# Power_and_Decoupling_Capacitors.net
KiCad netlist of a schematic drawn in Altium Designer
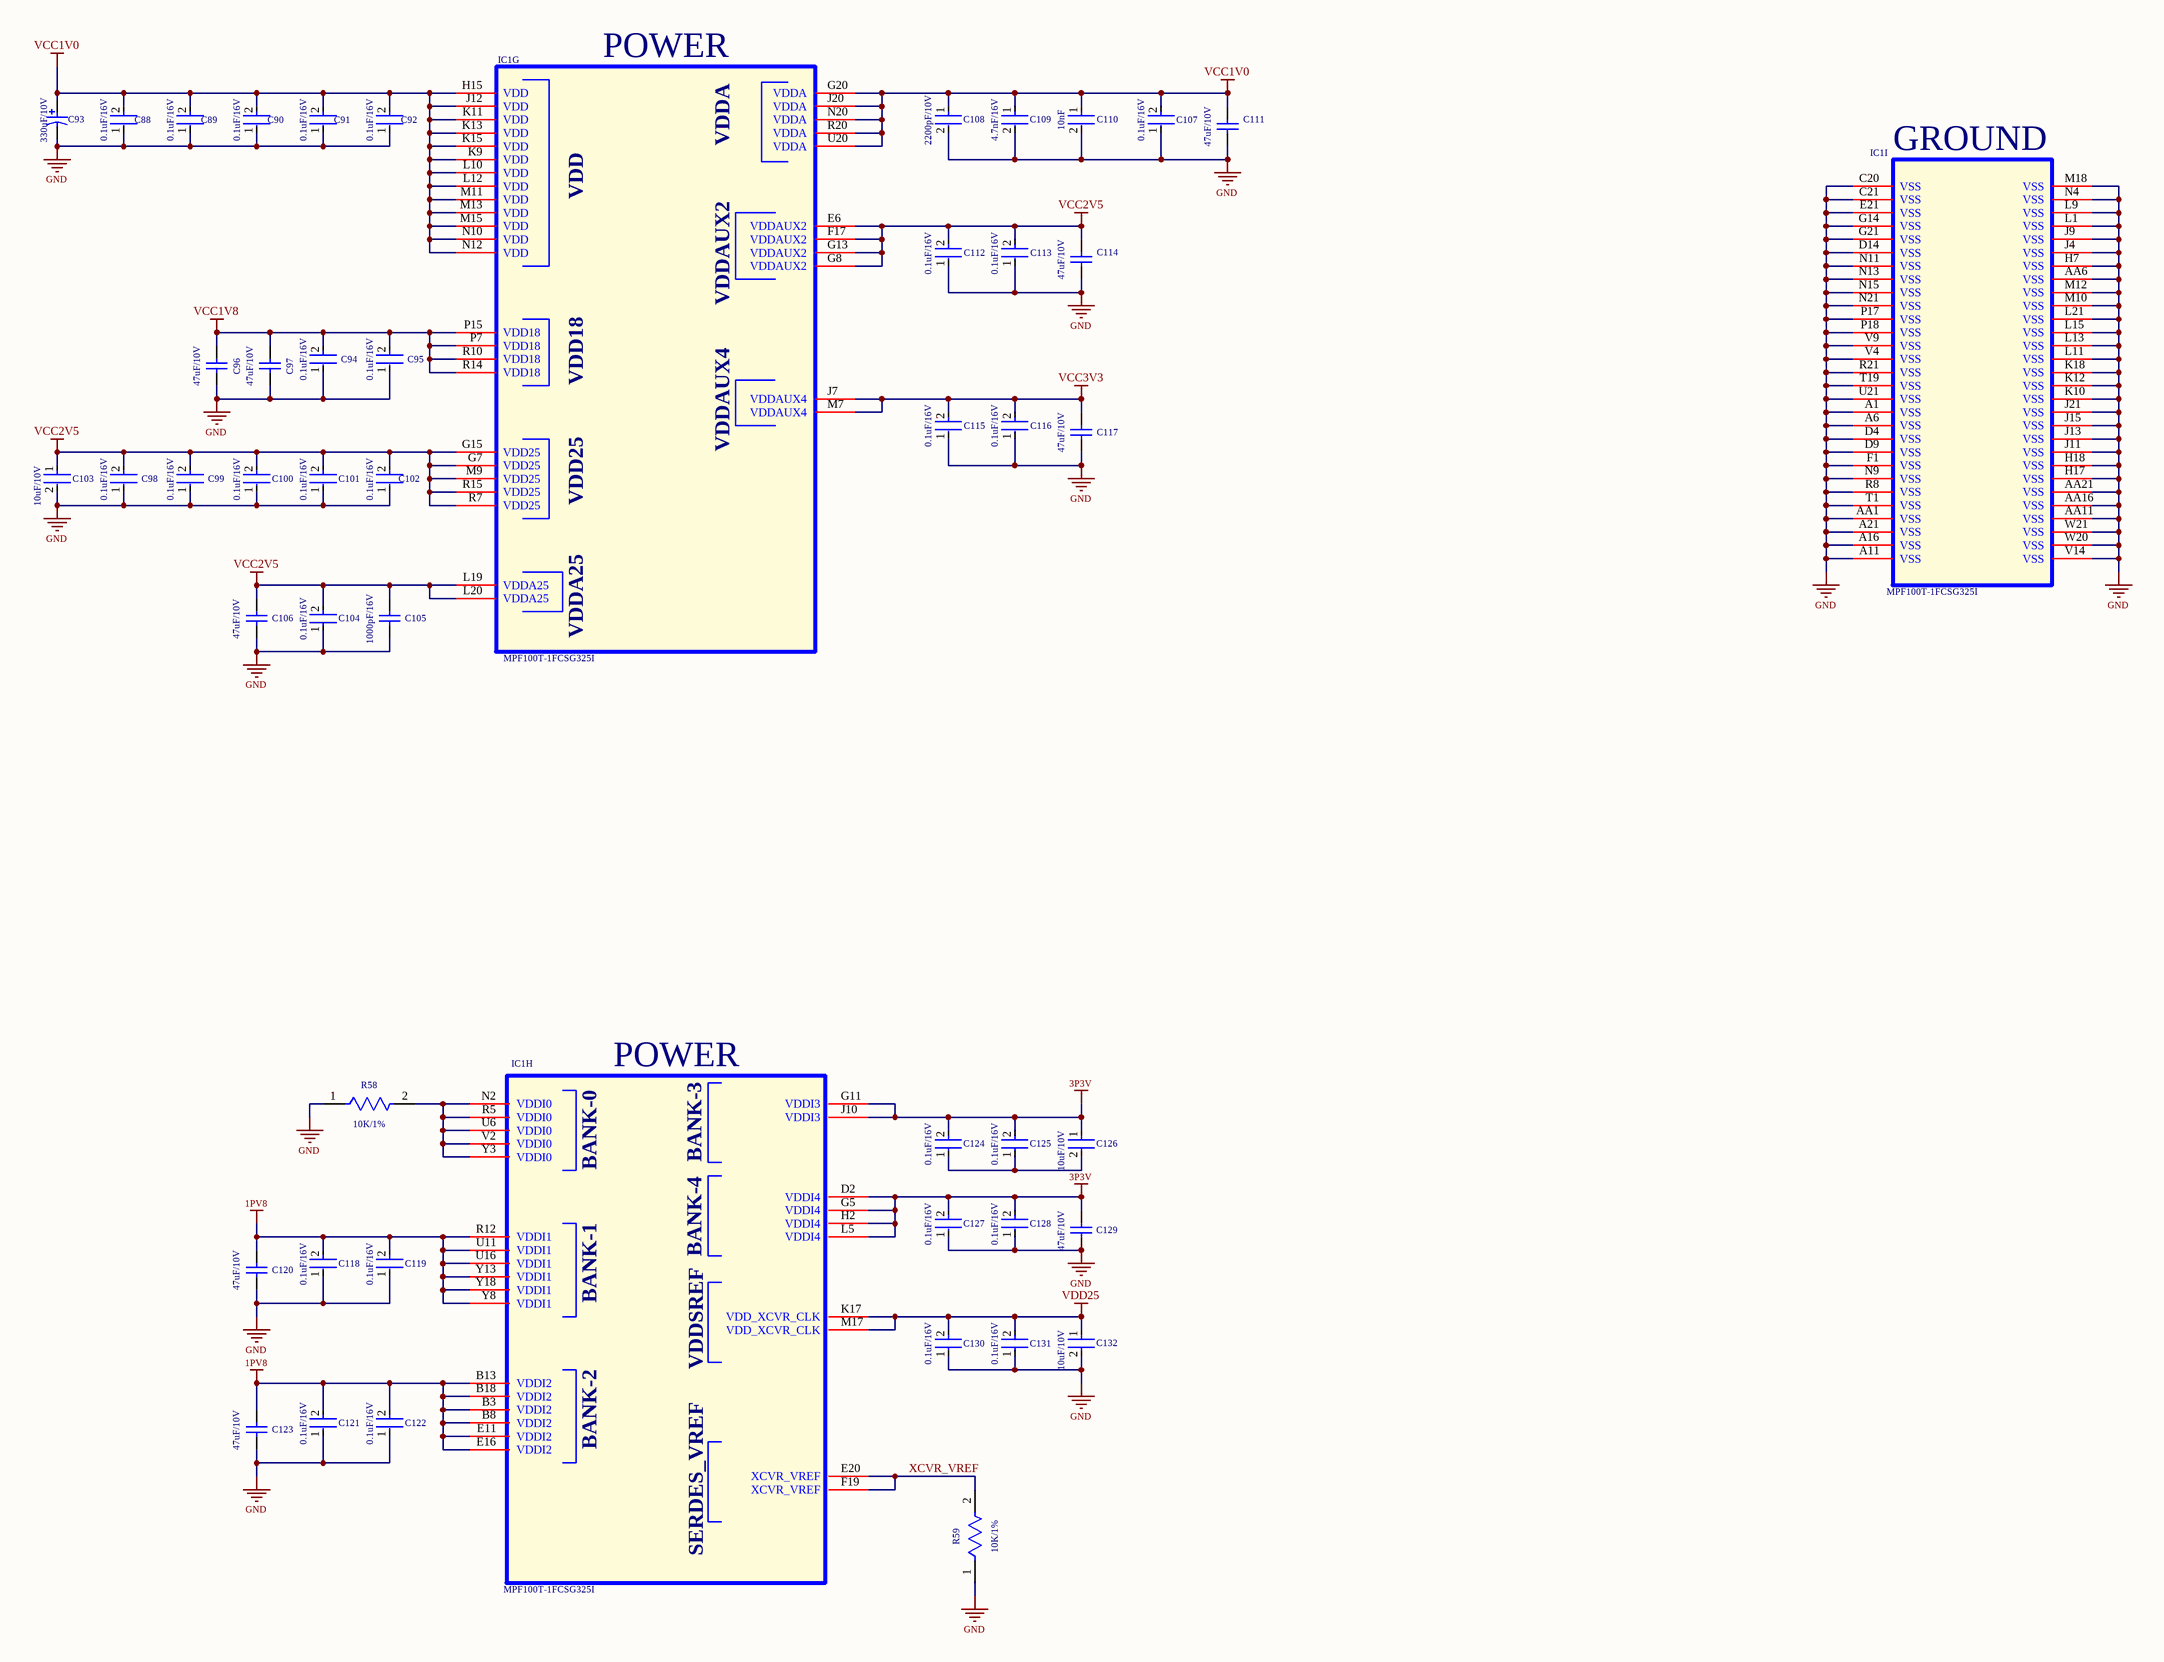
[diagram p0: Power and Decoupling Capacitors.SchDoc]

(export (version "E")
  (design (tool "Eeschema 10.0.6"))
  (components
    (comp (ref "C88")
      (value "0.1uF/16V")
      (footprint "FP-GRM15-MFG")
      (description "CAP CER 0.1UF 16V X7R 0402")
      (fields (field (name "MANUFACTURER PART NUMBER") "GRM155R71C104KA88D") (field (name "TOLERANCE") "10%"))
      (libsource (lib "Altium Content Vault") (part "236180d848d6139a670b325ea6854c9"))
    )
    (comp (ref "C89")
      (value "0.1uF/16V")
      (footprint "FP-GRM15-MFG")
      (description "CAP CER 0.1UF 16V X7R 0402")
      (fields (field (name "MANUFACTURER PART NUMBER") "GRM155R71C104KA88D") (field (name "TOLERANCE") "10%"))
      (libsource (lib "Altium Content Vault") (part "236180d848d6139a670b325ea6854c9"))
    )
    (comp (ref "C90")
      (value "0.1uF/16V")
      (footprint "FP-GRM15-MFG")
      (description "CAP CER 0.1UF 16V X7R 0402")
      (fields (field (name "MANUFACTURER PART NUMBER") "GRM155R71C104KA88D") (field (name "TOLERANCE") "10%"))
      (libsource (lib "Altium Content Vault") (part "236180d848d6139a670b325ea6854c9"))
    )
    (comp (ref "C91")
      (value "0.1uF/16V")
      (footprint "FP-GRM15-MFG")
      (description "CAP CER 0.1UF 16V X7R 0402")
      (fields (field (name "MANUFACTURER PART NUMBER") "GRM155R71C104KA88D") (field (name "TOLERANCE") "10%"))
      (libsource (lib "Altium Content Vault") (part "236180d848d6139a670b325ea6854c9"))
    )
    (comp (ref "C92")
      (value "0.1uF/16V")
      (footprint "FP-GRM15-MFG")
      (description "CAP CER 0.1UF 16V X7R 0402")
      (fields (field (name "MANUFACTURER PART NUMBER") "GRM155R71C104KA88D") (field (name "TOLERANCE") "10%"))
      (libsource (lib "Altium Content Vault") (part "236180d848d6139a670b325ea6854c9"))
    )
    (comp (ref "C93")
      (value "330uF/10V")
      (footprint "NIC-CAPA2-8X10_V")
      (fields (field (name "MANUFACTURER") "Nichicon") (field (name "PARTNUMBER") "UUD1C331MNL1GS"))
      (libsource (lib "Altium Content Vault") (part "NIC-CAP-P-2"))
    )
    (comp (ref "C94")
      (value "0.1uF/16V")
      (footprint "FP-GRM15-MFG")
      (description "CAP CER 0.1UF 16V X7R 0402")
      (fields (field (name "MANUFACTURER PART NUMBER") "GRM155R71C104KA88D") (field (name "TOLERANCE") "10%"))
      (libsource (lib "Altium Content Vault") (part "236180d848d6139a670b325ea6854c9"))
    )
    (comp (ref "C95")
      (value "0.1uF/16V")
      (footprint "FP-GRM15-MFG")
      (description "CAP CER 0.1UF 16V X7R 0402")
      (fields (field (name "MANUFACTURER PART NUMBER") "GRM155R71C104KA88D") (field (name "TOLERANCE") "10%"))
      (libsource (lib "Altium Content Vault") (part "236180d848d6139a670b325ea6854c9"))
    )
    (comp (ref "C96")
      (value "47uF/10V")
      (footprint "CAPC2014X135X70LL20")
      (fields
        (field (name "PART NUMBER") "TLCR476M010XTA")
        (field (name "MANUFACTURER") "AVX Interconnect / Elco")
      )
      (libsource (lib "Altium Content Vault") (part "CAP"))
    )
    (comp (ref "C97")
      (value "47uF/10V")
      (footprint "CAPC2014X135X70LL20")
      (fields
        (field (name "PART NUMBER") "TLCR476M010XTA")
        (field (name "MANUFACTURER") "AVX Interconnect / Elco")
      )
      (libsource (lib "Altium Content Vault") (part "CAP"))
    )
    (comp (ref "C98")
      (value "0.1uF/16V")
      (footprint "FP-GRM15-MFG")
      (description "CAP CER 0.1UF 16V X7R 0402")
      (fields (field (name "MANUFACTURER PART NUMBER") "GRM155R71C104KA88D") (field (name "TOLERANCE") "10%"))
      (libsource (lib "Altium Content Vault") (part "236180d848d6139a670b325ea6854c9"))
    )
    (comp (ref "C99")
      (value "0.1uF/16V")
      (footprint "FP-GRM15-MFG")
      (description "CAP CER 0.1UF 16V X7R 0402")
      (fields (field (name "MANUFACTURER PART NUMBER") "GRM155R71C104KA88D") (field (name "TOLERANCE") "10%"))
      (libsource (lib "Altium Content Vault") (part "236180d848d6139a670b325ea6854c9"))
    )
    (comp (ref "C100")
      (value "0.1uF/16V")
      (footprint "FP-GRM15-MFG")
      (description "CAP CER 0.1UF 16V X7R 0402")
      (fields (field (name "MANUFACTURER PART NUMBER") "GRM155R71C104KA88D") (field (name "TOLERANCE") "10%"))
      (libsource (lib "Altium Content Vault") (part "236180d848d6139a670b325ea6854c9"))
    )
    (comp (ref "C101")
      (value "0.1uF/16V")
      (footprint "FP-GRM15-MFG")
      (description "CAP CER 0.1UF 16V X7R 0402")
      (fields (field (name "MANUFACTURER PART NUMBER") "GRM155R71C104KA88D") (field (name "TOLERANCE") "10%"))
      (libsource (lib "Altium Content Vault") (part "236180d848d6139a670b325ea6854c9"))
    )
    (comp (ref "C102")
      (value "0.1uF/16V")
      (footprint "FP-GRM15-MFG")
      (description "CAP CER 0.1UF 16V X7R 0402")
      (fields (field (name "MANUFACTURER PART NUMBER") "GRM155R71C104KA88D") (field (name "TOLERANCE") "10%"))
      (libsource (lib "Altium Content Vault") (part "236180d848d6139a670b325ea6854c9"))
    )
    (comp (ref "C103")
      (value "10uF/10V")
      (footprint "FP-CL05A106MP5NUNC-MFG")
      (description "CAP CER 10UF 10V X5R 0402")
      (fields
        (field (name "OCTOPART") "https://octopart.com/cl05a106mp5nunc-samsung-22457395")
        (field (name "TOLERANCE") "20%")
      )
      (libsource (lib "Altium Content Vault") (part "b4654b650e69147ec39a6b967a45e02"))
    )
    (comp (ref "C104")
      (value "0.1uF/16V")
      (footprint "FP-GRM15-MFG")
      (description "CAP CER 0.1UF 16V X7R 0402")
      (fields (field (name "MANUFACTURER PART NUMBER") "GRM155R71C104KA88D") (field (name "TOLERANCE") "10%"))
      (libsource (lib "Altium Content Vault") (part "236180d848d6139a670b325ea6854c9"))
    )
    (comp (ref "C105")
      (value "1000pF/16V")
      (footprint "CAPC0603X33X15LL03T05")
      (fields
        (field (name "PART NUMBER") "02013D102KAT2A")
        (field (name "MANUFACTURER") "AVX Interconnect / Elco")
      )
      (libsource (lib "Altium Content Vault") (part "CAP"))
    )
    (comp (ref "C106")
      (value "47uF/10V")
      (footprint "CAPC2014X135X70LL20")
      (fields
        (field (name "PART NUMBER") "TLCR476M010XTA")
        (field (name "MANUFACTURER") "AVX Interconnect / Elco")
      )
      (libsource (lib "Altium Content Vault") (part "CAP"))
    )
    (comp (ref "C107")
      (value "0.1uF/16V")
      (footprint "FP-GRM15-MFG")
      (description "CAP CER 0.1UF 16V X7R 0402")
      (fields (field (name "MANUFACTURER PART NUMBER") "GRM155R71C104KA88D") (field (name "TOLERANCE") "10%"))
      (libsource (lib "Altium Content Vault") (part "236180d848d6139a670b325ea6854c9"))
    )
    (comp (ref "C108")
      (value "2200pF/10V")
      (footprint "FP-C0402-BB-MFG")
      (description "CAP CER 2200PF 25V 5% NP0 0402")
      (fields
        (field (name "OCTOPART") "https://octopart.com/c0402c222j3gactu-kemet-9145102")
        (field (name "MANUFACTURER") "Kemet")
      )
      (libsource (lib "Altium Content Vault") (part "b4654b650e69147ec39a6b967a45e02"))
    )
    (comp (ref "C109")
      (value "4.7nF/16V")
      (footprint "FP-CC0201-BA-MFG")
      (description "CAP CER 4700PF 16V X7R 0201")
      (fields
        (field (name "MANUFACTURER PART NUMBER") "CC0201KRX7R7BB472")
        (field (name "OCTOPART") "https://octopart.com/cc0201krx7r7bb472-yageo-33242265")
      )
      (libsource (lib "Altium Content Vault") (part "11868f565c42a9108669ba33697ecf6"))
    )
    (comp (ref "C110")
      (value "10nF")
      (footprint "FP-0402-L_1_0_1-W_0_5_0_1-IPC_B")
      (description "General Purpose Ceramic Capacitor, 0402, 10nF, 5%, X7R, 15%, 16V")
      (fields (field (name "VOLTAGE") "16V") (field (name "TOLERANCE") "5%"))
      (libsource (lib "Altium Content Vault") (part "b4654b650e69147ec39a6b967a45e02"))
    )
    (comp (ref "C111")
      (value "47uF/10V")
      (footprint "CAPC2014X135X70LL20")
      (fields
        (field (name "PART NUMBER") "TLCR476M010XTA")
        (field (name "MANUFACTURER") "AVX Interconnect / Elco")
      )
      (libsource (lib "Altium Content Vault") (part "CAP"))
    )
    (comp (ref "C112")
      (value "0.1uF/16V")
      (footprint "FP-GRM15-MFG")
      (description "CAP CER 0.1UF 16V X7R 0402")
      (fields (field (name "MANUFACTURER PART NUMBER") "GRM155R71C104KA88D") (field (name "TOLERANCE") "10%"))
      (libsource (lib "Altium Content Vault") (part "236180d848d6139a670b325ea6854c9"))
    )
    (comp (ref "C113")
      (value "0.1uF/16V")
      (footprint "FP-GRM15-MFG")
      (description "CAP CER 0.1UF 16V X7R 0402")
      (fields (field (name "MANUFACTURER PART NUMBER") "GRM155R71C104KA88D") (field (name "TOLERANCE") "10%"))
      (libsource (lib "Altium Content Vault") (part "236180d848d6139a670b325ea6854c9"))
    )
    (comp (ref "C114")
      (value "47uF/10V")
      (footprint "CAPC2014X135X70LL20")
      (fields
        (field (name "PART NUMBER") "TLCR476M010XTA")
        (field (name "MANUFACTURER") "AVX Interconnect / Elco")
      )
      (libsource (lib "Altium Content Vault") (part "CAP"))
    )
    (comp (ref "C115")
      (value "0.1uF/16V")
      (footprint "FP-GRM15-MFG")
      (description "CAP CER 0.1UF 16V X7R 0402")
      (fields (field (name "MANUFACTURER PART NUMBER") "GRM155R71C104KA88D") (field (name "TOLERANCE") "10%"))
      (libsource (lib "Altium Content Vault") (part "236180d848d6139a670b325ea6854c9"))
    )
    (comp (ref "C116")
      (value "0.1uF/16V")
      (footprint "FP-GRM15-MFG")
      (description "CAP CER 0.1UF 16V X7R 0402")
      (fields (field (name "MANUFACTURER PART NUMBER") "GRM155R71C104KA88D") (field (name "TOLERANCE") "10%"))
      (libsource (lib "Altium Content Vault") (part "236180d848d6139a670b325ea6854c9"))
    )
    (comp (ref "C117")
      (value "47uF/10V")
      (footprint "CAPC2014X135X70LL20")
      (fields
        (field (name "PART NUMBER") "TLCR476M010XTA")
        (field (name "MANUFACTURER") "AVX Interconnect / Elco")
      )
      (libsource (lib "Altium Content Vault") (part "CAP"))
    )
    (comp (ref "C118")
      (value "0.1uF/16V")
      (footprint "FP-GRM15-MFG")
      (description "CAP CER 0.1UF 16V X7R 0402")
      (fields (field (name "MANUFACTURER PART NUMBER") "GRM155R71C104KA88D") (field (name "TOLERANCE") "10%"))
      (libsource (lib "Altium Content Vault") (part "236180d848d6139a670b325ea6854c9"))
    )
    (comp (ref "C119")
      (value "0.1uF/16V")
      (footprint "FP-GRM15-MFG")
      (description "CAP CER 0.1UF 16V X7R 0402")
      (fields (field (name "MANUFACTURER PART NUMBER") "GRM155R71C104KA88D") (field (name "TOLERANCE") "10%"))
      (libsource (lib "Altium Content Vault") (part "236180d848d6139a670b325ea6854c9"))
    )
    (comp (ref "C120")
      (value "47uF/10V")
      (footprint "CAPC2014X135X70LL20")
      (fields
        (field (name "PART NUMBER") "TLCR476M010XTA")
        (field (name "MANUFACTURER") "AVX Interconnect / Elco")
      )
      (libsource (lib "Altium Content Vault") (part "CAP"))
    )
    (comp (ref "C121")
      (value "0.1uF/16V")
      (footprint "FP-GRM15-MFG")
      (description "CAP CER 0.1UF 16V X7R 0402")
      (fields (field (name "MANUFACTURER PART NUMBER") "GRM155R71C104KA88D") (field (name "TOLERANCE") "10%"))
      (libsource (lib "Altium Content Vault") (part "236180d848d6139a670b325ea6854c9"))
    )
    (comp (ref "C122")
      (value "0.1uF/16V")
      (footprint "FP-GRM15-MFG")
      (description "CAP CER 0.1UF 16V X7R 0402")
      (fields (field (name "MANUFACTURER PART NUMBER") "GRM155R71C104KA88D") (field (name "TOLERANCE") "10%"))
      (libsource (lib "Altium Content Vault") (part "236180d848d6139a670b325ea6854c9"))
    )
    (comp (ref "C123")
      (value "47uF/10V")
      (footprint "CAPC2014X135X70LL20")
      (fields
        (field (name "PART NUMBER") "TLCR476M010XTA")
        (field (name "MANUFACTURER") "AVX Interconnect / Elco")
      )
      (libsource (lib "Altium Content Vault") (part "CAP"))
    )
    (comp (ref "C124")
      (value "0.1uF/16V")
      (footprint "FP-GRM15-MFG")
      (description "CAP CER 0.1UF 16V X7R 0402")
      (fields (field (name "MANUFACTURER PART NUMBER") "GRM155R71C104KA88D") (field (name "TOLERANCE") "10%"))
      (libsource (lib "Altium Content Vault") (part "236180d848d6139a670b325ea6854c9"))
    )
    (comp (ref "C125")
      (value "0.1uF/16V")
      (footprint "FP-GRM15-MFG")
      (description "CAP CER 0.1UF 16V X7R 0402")
      (fields (field (name "MANUFACTURER PART NUMBER") "GRM155R71C104KA88D") (field (name "TOLERANCE") "10%"))
      (libsource (lib "Altium Content Vault") (part "236180d848d6139a670b325ea6854c9"))
    )
    (comp (ref "C126")
      (value "10uF/10V")
      (footprint "FP-CL05A106MP5NUNC-MFG")
      (description "CAP CER 10UF 10V X5R 0402")
      (fields
        (field (name "OCTOPART") "https://octopart.com/cl05a106mp5nunc-samsung-22457395")
        (field (name "TOLERANCE") "20%")
      )
      (libsource (lib "Altium Content Vault") (part "b4654b650e69147ec39a6b967a45e02"))
    )
    (comp (ref "C127")
      (value "0.1uF/16V")
      (footprint "FP-GRM15-MFG")
      (description "CAP CER 0.1UF 16V X7R 0402")
      (fields (field (name "MANUFACTURER PART NUMBER") "GRM155R71C104KA88D") (field (name "TOLERANCE") "10%"))
      (libsource (lib "Altium Content Vault") (part "236180d848d6139a670b325ea6854c9"))
    )
    (comp (ref "C128")
      (value "0.1uF/16V")
      (footprint "FP-GRM15-MFG")
      (description "CAP CER 0.1UF 16V X7R 0402")
      (fields (field (name "MANUFACTURER PART NUMBER") "GRM155R71C104KA88D") (field (name "TOLERANCE") "10%"))
      (libsource (lib "Altium Content Vault") (part "236180d848d6139a670b325ea6854c9"))
    )
    (comp (ref "C129")
      (value "47uF/10V")
      (footprint "CAPC2014X135X70LL20")
      (fields
        (field (name "PART NUMBER") "TLCR476M010XTA")
        (field (name "MANUFACTURER") "AVX Interconnect / Elco")
      )
      (libsource (lib "Altium Content Vault") (part "CAP"))
    )
    (comp (ref "C130")
      (value "0.1uF/16V")
      (footprint "FP-GRM15-MFG")
      (description "CAP CER 0.1UF 16V X7R 0402")
      (fields (field (name "MANUFACTURER PART NUMBER") "GRM155R71C104KA88D") (field (name "TOLERANCE") "10%"))
      (libsource (lib "Altium Content Vault") (part "236180d848d6139a670b325ea6854c9"))
    )
    (comp (ref "C131")
      (value "0.1uF/16V")
      (footprint "FP-GRM15-MFG")
      (description "CAP CER 0.1UF 16V X7R 0402")
      (fields (field (name "MANUFACTURER PART NUMBER") "GRM155R71C104KA88D") (field (name "TOLERANCE") "10%"))
      (libsource (lib "Altium Content Vault") (part "236180d848d6139a670b325ea6854c9"))
    )
    (comp (ref "C132")
      (value "10uF/10V")
      (footprint "FP-CL05A106MP5NUNC-MFG")
      (description "CAP CER 10UF 10V X5R 0402")
      (fields
        (field (name "OCTOPART") "https://octopart.com/cl05a106mp5nunc-samsung-22457395")
        (field (name "TOLERANCE") "20%")
      )
      (libsource (lib "Altium Content Vault") (part "b4654b650e69147ec39a6b967a45e02"))
    )
    (comp (ref "IC1")
      (value "MPF100T-1FCSG325I")
      (footprint "PCB_Display_Doru:MPF100T-1FCSG325I")
      (fields (field (name "PART_NUMBER") "J00001"))
      (libsource (lib "PCB_Display_Doru") (part "MPF100T-1FCSG325I"))
    )
    (comp (ref "R58")
      (value "10K/1%")
      (footprint "FP-RC0603-0_55-IPC_C")
      (description "RES 10K OHM 1% 1/10W 0603")
      (fields (field (name "TOLERANCE") "1%"))
      (libsource (lib "Altium Content Vault") (part "1029c3af85768c4190bb7ad29bc67b5"))
    )
    (comp (ref "R59")
      (value "10K/1%")
      (footprint "FP-RC0603-0_55-IPC_C")
      (description "RES 10K OHM 1% 1/10W 0603")
      (fields (field (name "TOLERANCE") "1%"))
      (libsource (lib "Altium Content Vault") (part "1029c3af85768c4190bb7ad29bc67b5"))
    )
  )
  (nets
    (net (code "1") (name "/XCVR_VREF") (class "Default")
      (node (ref "IC1") (pin "E20") (pinfunction "XCVR_VREF_E20") (pintype "power_in"))
      (node (ref "IC1") (pin "F19") (pinfunction "XCVR_VREF_F19") (pintype "power_in"))
      (node (ref "R59") (pin "2") (pinfunction "2_2") (pintype "passive"))
    )
    (net (code "2") (name "1PV8") (class "Default")
      (node (ref "C118") (pin "2") (pinfunction "2_2") (pintype "passive"))
      (node (ref "C119") (pin "2") (pinfunction "2_2") (pintype "passive"))
      (node (ref "C120") (pin "1") (pinfunction "1_1") (pintype "passive"))
      (node (ref "C121") (pin "2") (pinfunction "2_2") (pintype "passive"))
      (node (ref "C122") (pin "2") (pinfunction "2_2") (pintype "passive"))
      (node (ref "C123") (pin "1") (pinfunction "1_1") (pintype "passive"))
      (node (ref "IC1") (pin "B13") (pinfunction "VDDI2_B13") (pintype "power_in"))
      (node (ref "IC1") (pin "B18") (pinfunction "VDDI2_B18") (pintype "power_in"))
      (node (ref "IC1") (pin "B3") (pinfunction "VDDI2_B3") (pintype "power_in"))
      (node (ref "IC1") (pin "B8") (pinfunction "VDDI2_B8") (pintype "power_in"))
      (node (ref "IC1") (pin "E11") (pinfunction "VDDI2_E11") (pintype "power_in"))
      (node (ref "IC1") (pin "E16") (pinfunction "VDDI2_E16") (pintype "power_in"))
      (node (ref "IC1") (pin "R12") (pinfunction "VDDI1_R12") (pintype "power_in"))
      (node (ref "IC1") (pin "U11") (pinfunction "VDDI1_U11") (pintype "power_in"))
      (node (ref "IC1") (pin "U16") (pinfunction "VDDI1_U16") (pintype "power_in"))
      (node (ref "IC1") (pin "Y13") (pinfunction "VDDI1_Y13") (pintype "power_in"))
      (node (ref "IC1") (pin "Y18") (pinfunction "VDDI1_Y18") (pintype "power_in"))
      (node (ref "IC1") (pin "Y8") (pinfunction "VDDI1_Y8") (pintype "power_in"))
    )
    (net (code "3") (name "3P3V") (class "Default")
      (node (ref "C124") (pin "2") (pinfunction "2_2") (pintype "passive"))
      (node (ref "C125") (pin "2") (pinfunction "2_2") (pintype "passive"))
      (node (ref "C126") (pin "1") (pinfunction "1_1") (pintype "passive"))
      (node (ref "C127") (pin "2") (pinfunction "2_2") (pintype "passive"))
      (node (ref "C128") (pin "2") (pinfunction "2_2") (pintype "passive"))
      (node (ref "C129") (pin "1") (pinfunction "1_1") (pintype "passive"))
      (node (ref "IC1") (pin "D2") (pinfunction "VDDI4_D2") (pintype "power_in"))
      (node (ref "IC1") (pin "G11") (pinfunction "VDDI3_G11") (pintype "power_in"))
      (node (ref "IC1") (pin "G5") (pinfunction "VDDI4_G5") (pintype "power_in"))
      (node (ref "IC1") (pin "H2") (pinfunction "VDDI4_H2") (pintype "power_in"))
      (node (ref "IC1") (pin "J10") (pinfunction "VDDI3_J10") (pintype "power_in"))
      (node (ref "IC1") (pin "L5") (pinfunction "VDDI4_L5") (pintype "power_in"))
    )
    (net (code "4") (name "GND") (class "Default")
      (node (ref "C100") (pin "1") (pinfunction "1_1") (pintype "passive"))
      (node (ref "C101") (pin "1") (pinfunction "1_1") (pintype "passive"))
      (node (ref "C102") (pin "1") (pinfunction "1_1") (pintype "passive"))
      (node (ref "C103") (pin "2") (pinfunction "2_2") (pintype "passive"))
      (node (ref "C104") (pin "1") (pinfunction "1_1") (pintype "passive"))
      (node (ref "C105") (pin "1") (pinfunction "1_1") (pintype "passive"))
      (node (ref "C106") (pin "2") (pinfunction "2_2") (pintype "passive"))
      (node (ref "C107") (pin "1") (pinfunction "1_1") (pintype "passive"))
      (node (ref "C108") (pin "2") (pinfunction "2_2") (pintype "passive"))
      (node (ref "C109") (pin "2") (pinfunction "2_2") (pintype "passive"))
      (node (ref "C110") (pin "2") (pinfunction "2_2") (pintype "passive"))
      (node (ref "C111") (pin "2") (pinfunction "2_2") (pintype "passive"))
      (node (ref "C112") (pin "1") (pinfunction "1_1") (pintype "passive"))
      (node (ref "C113") (pin "1") (pinfunction "1_1") (pintype "passive"))
      (node (ref "C114") (pin "2") (pinfunction "2_2") (pintype "passive"))
      (node (ref "C115") (pin "1") (pinfunction "1_1") (pintype "passive"))
      (node (ref "C116") (pin "1") (pinfunction "1_1") (pintype "passive"))
      (node (ref "C117") (pin "2") (pinfunction "2_2") (pintype "passive"))
      (node (ref "C118") (pin "1") (pinfunction "1_1") (pintype "passive"))
      (node (ref "C119") (pin "1") (pinfunction "1_1") (pintype "passive"))
      (node (ref "C120") (pin "2") (pinfunction "2_2") (pintype "passive"))
      (node (ref "C121") (pin "1") (pinfunction "1_1") (pintype "passive"))
      (node (ref "C122") (pin "1") (pinfunction "1_1") (pintype "passive"))
      (node (ref "C123") (pin "2") (pinfunction "2_2") (pintype "passive"))
      (node (ref "C127") (pin "1") (pinfunction "1_1") (pintype "passive"))
      (node (ref "C128") (pin "1") (pinfunction "1_1") (pintype "passive"))
      (node (ref "C129") (pin "2") (pinfunction "2_2") (pintype "passive"))
      (node (ref "C130") (pin "1") (pinfunction "1_1") (pintype "passive"))
      (node (ref "C131") (pin "1") (pinfunction "1_1") (pintype "passive"))
      (node (ref "C132") (pin "2") (pinfunction "2_2") (pintype "passive"))
      (node (ref "C88") (pin "1") (pinfunction "1_1") (pintype "passive"))
      (node (ref "C89") (pin "1") (pinfunction "1_1") (pintype "passive"))
      (node (ref "C90") (pin "1") (pinfunction "1_1") (pintype "passive"))
      (node (ref "C91") (pin "1") (pinfunction "1_1") (pintype "passive"))
      (node (ref "C92") (pin "1") (pinfunction "1_1") (pintype "passive"))
      (node (ref "C93") (pin "2") (pinfunction "2_2") (pintype "passive"))
      (node (ref "C94") (pin "1") (pinfunction "1_1") (pintype "passive"))
      (node (ref "C95") (pin "1") (pinfunction "1_1") (pintype "passive"))
      (node (ref "C96") (pin "2") (pinfunction "2_2") (pintype "passive"))
      (node (ref "C97") (pin "2") (pinfunction "2_2") (pintype "passive"))
      (node (ref "C98") (pin "1") (pinfunction "1_1") (pintype "passive"))
      (node (ref "C99") (pin "1") (pinfunction "1_1") (pintype "passive"))
      (node (ref "IC1") (pin "A1") (pinfunction "VSS_A1") (pintype "power_in"))
      (node (ref "IC1") (pin "A11") (pinfunction "VSS_A11") (pintype "power_in"))
      (node (ref "IC1") (pin "A16") (pinfunction "VSS_A16") (pintype "power_in"))
      (node (ref "IC1") (pin "A21") (pinfunction "VSS_A21") (pintype "power_in"))
      (node (ref "IC1") (pin "A6") (pinfunction "VSS_A6") (pintype "power_in"))
      (node (ref "IC1") (pin "AA1") (pinfunction "VSS_AA1") (pintype "power_in"))
      (node (ref "IC1") (pin "AA11") (pinfunction "VSS_AA11") (pintype "power_in"))
      (node (ref "IC1") (pin "AA16") (pinfunction "VSS_AA16") (pintype "power_in"))
      (node (ref "IC1") (pin "AA21") (pinfunction "VSS_AA21") (pintype "power_in"))
      (node (ref "IC1") (pin "AA6") (pinfunction "VSS_AA6") (pintype "power_in"))
      (node (ref "IC1") (pin "C20") (pinfunction "VSS_C20") (pintype "power_in"))
      (node (ref "IC1") (pin "C21") (pinfunction "VSS_C21") (pintype "power_in"))
      (node (ref "IC1") (pin "D14") (pinfunction "VSS_D14") (pintype "power_in"))
      (node (ref "IC1") (pin "D4") (pinfunction "VSS_D4") (pintype "power_in"))
      (node (ref "IC1") (pin "D9") (pinfunction "VSS_D9") (pintype "power_in"))
      (node (ref "IC1") (pin "E21") (pinfunction "VSS_E21") (pintype "power_in"))
      (node (ref "IC1") (pin "F1") (pinfunction "VSS_F1") (pintype "power_in"))
      (node (ref "IC1") (pin "G14") (pinfunction "VSS_G14") (pintype "power_in"))
      (node (ref "IC1") (pin "G21") (pinfunction "VSS_G21") (pintype "power_in"))
      (node (ref "IC1") (pin "H17") (pinfunction "VSS_H17") (pintype "power_in"))
      (node (ref "IC1") (pin "H18") (pinfunction "VSS_H18") (pintype "power_in"))
      (node (ref "IC1") (pin "H7") (pinfunction "VSS_H7") (pintype "power_in"))
      (node (ref "IC1") (pin "J11") (pinfunction "VSS_J11") (pintype "power_in"))
      (node (ref "IC1") (pin "J13") (pinfunction "VSS_J13") (pintype "power_in"))
      (node (ref "IC1") (pin "J15") (pinfunction "VSS_J15") (pintype "power_in"))
      (node (ref "IC1") (pin "J21") (pinfunction "VSS_J21") (pintype "power_in"))
      (node (ref "IC1") (pin "J4") (pinfunction "VSS_J4") (pintype "power_in"))
      (node (ref "IC1") (pin "J9") (pinfunction "VSS_J9") (pintype "power_in"))
      (node (ref "IC1") (pin "K10") (pinfunction "VSS_K10") (pintype "power_in"))
      (node (ref "IC1") (pin "K12") (pinfunction "VSS_K12") (pintype "power_in"))
      (node (ref "IC1") (pin "K18") (pinfunction "VSS_K18") (pintype "power_in"))
      (node (ref "IC1") (pin "L1") (pinfunction "VSS_L1") (pintype "power_in"))
      (node (ref "IC1") (pin "L11") (pinfunction "VSS_L11") (pintype "power_in"))
      (node (ref "IC1") (pin "L13") (pinfunction "VSS_L13") (pintype "power_in"))
      (node (ref "IC1") (pin "L15") (pinfunction "VSS_L15") (pintype "power_in"))
      (node (ref "IC1") (pin "L21") (pinfunction "VSS_L21") (pintype "power_in"))
      (node (ref "IC1") (pin "L9") (pinfunction "VSS_L9") (pintype "power_in"))
      (node (ref "IC1") (pin "M10") (pinfunction "VSS_M10") (pintype "power_in"))
      (node (ref "IC1") (pin "M12") (pinfunction "VSS_M12") (pintype "power_in"))
      (node (ref "IC1") (pin "M18") (pinfunction "VSS_M18") (pintype "power_in"))
      (node (ref "IC1") (pin "N11") (pinfunction "VSS_N11") (pintype "power_in"))
      (node (ref "IC1") (pin "N13") (pinfunction "VSS_N13") (pintype "power_in"))
      (node (ref "IC1") (pin "N15") (pinfunction "VSS_N15") (pintype "power_in"))
      (node (ref "IC1") (pin "N21") (pinfunction "VSS_N21") (pintype "power_in"))
      (node (ref "IC1") (pin "N4") (pinfunction "VSS_N4") (pintype "power_in"))
      (node (ref "IC1") (pin "N9") (pinfunction "VSS_N9") (pintype "power_in"))
      (node (ref "IC1") (pin "P17") (pinfunction "VSS_P17") (pintype "power_in"))
      (node (ref "IC1") (pin "P18") (pinfunction "VSS_P18") (pintype "power_in"))
      (node (ref "IC1") (pin "R21") (pinfunction "VSS_R21") (pintype "power_in"))
      (node (ref "IC1") (pin "R8") (pinfunction "VSS_R8") (pintype "power_in"))
      (node (ref "IC1") (pin "T1") (pinfunction "VSS_T1") (pintype "power_in"))
      (node (ref "IC1") (pin "T19") (pinfunction "VSS_T19") (pintype "power_in"))
      (node (ref "IC1") (pin "U21") (pinfunction "VSS_U21") (pintype "power_in"))
      (node (ref "IC1") (pin "V14") (pinfunction "VSS_V14") (pintype "power_in"))
      (node (ref "IC1") (pin "V4") (pinfunction "VSS_V4") (pintype "power_in"))
      (node (ref "IC1") (pin "V9") (pinfunction "VSS_V9") (pintype "power_in"))
      (node (ref "IC1") (pin "W20") (pinfunction "VSS_W20") (pintype "power_in"))
      (node (ref "IC1") (pin "W21") (pinfunction "VSS_W21") (pintype "power_in"))
      (node (ref "R58") (pin "1") (pinfunction "1_1") (pintype "passive"))
      (node (ref "R59") (pin "1") (pinfunction "1_1") (pintype "passive"))
    )
    (net (code "5") (name "Net-(C124-Pad1)") (class "Default")
      (node (ref "C124") (pin "1") (pinfunction "1_1") (pintype "passive"))
      (node (ref "C125") (pin "1") (pinfunction "1_1") (pintype "passive"))
      (node (ref "C126") (pin "2") (pinfunction "2_2") (pintype "passive"))
    )
    (net (code "6") (name "Net-(IC1H-VDDI0-PadN2)") (class "Default")
      (node (ref "IC1") (pin "N2") (pinfunction "VDDI0_N2") (pintype "power_in"))
      (node (ref "IC1") (pin "R5") (pinfunction "VDDI0_R5") (pintype "power_in"))
      (node (ref "IC1") (pin "U6") (pinfunction "VDDI0_U6") (pintype "power_in"))
      (node (ref "IC1") (pin "V2") (pinfunction "VDDI0_V2") (pintype "power_in"))
      (node (ref "IC1") (pin "Y3") (pinfunction "VDDI0_Y3") (pintype "power_in"))
      (node (ref "R58") (pin "2") (pinfunction "2_2") (pintype "passive"))
    )
    (net (code "7") (name "VCC1V0") (class "Default")
      (node (ref "C107") (pin "2") (pinfunction "2_2") (pintype "passive"))
      (node (ref "C108") (pin "1") (pinfunction "1_1") (pintype "passive"))
      (node (ref "C109") (pin "1") (pinfunction "1_1") (pintype "passive"))
      (node (ref "C110") (pin "1") (pinfunction "1_1") (pintype "passive"))
      (node (ref "C111") (pin "1") (pinfunction "1_1") (pintype "passive"))
      (node (ref "C88") (pin "2") (pinfunction "2_2") (pintype "passive"))
      (node (ref "C89") (pin "2") (pinfunction "2_2") (pintype "passive"))
      (node (ref "C90") (pin "2") (pinfunction "2_2") (pintype "passive"))
      (node (ref "C91") (pin "2") (pinfunction "2_2") (pintype "passive"))
      (node (ref "C92") (pin "2") (pinfunction "2_2") (pintype "passive"))
      (node (ref "C93") (pin "1") (pinfunction "1_1") (pintype "passive"))
      (node (ref "IC1") (pin "G20") (pinfunction "VDDA_G20") (pintype "power_in"))
      (node (ref "IC1") (pin "H15") (pinfunction "VDD_H15") (pintype "power_in"))
      (node (ref "IC1") (pin "J12") (pinfunction "VDD_J12") (pintype "power_in"))
      (node (ref "IC1") (pin "J20") (pinfunction "VDDA_J20") (pintype "power_in"))
      (node (ref "IC1") (pin "K11") (pinfunction "VDD_K11") (pintype "power_in"))
      (node (ref "IC1") (pin "K13") (pinfunction "VDD_K13") (pintype "power_in"))
      (node (ref "IC1") (pin "K15") (pinfunction "VDD_K15") (pintype "power_in"))
      (node (ref "IC1") (pin "K9") (pinfunction "VDD_K9") (pintype "power_in"))
      (node (ref "IC1") (pin "L10") (pinfunction "VDD_L10") (pintype "power_in"))
      (node (ref "IC1") (pin "L12") (pinfunction "VDD_L12") (pintype "power_in"))
      (node (ref "IC1") (pin "M11") (pinfunction "VDD_M11") (pintype "power_in"))
      (node (ref "IC1") (pin "M13") (pinfunction "VDD_M13") (pintype "power_in"))
      (node (ref "IC1") (pin "M15") (pinfunction "VDD_M15") (pintype "power_in"))
      (node (ref "IC1") (pin "N10") (pinfunction "VDD_N10") (pintype "power_in"))
      (node (ref "IC1") (pin "N12") (pinfunction "VDD_N12") (pintype "power_in"))
      (node (ref "IC1") (pin "N20") (pinfunction "VDDA_N20") (pintype "power_in"))
      (node (ref "IC1") (pin "R20") (pinfunction "VDDA_R20") (pintype "power_in"))
      (node (ref "IC1") (pin "U20") (pinfunction "VDDA_U20") (pintype "power_in"))
    )
    (net (code "8") (name "VCC1V8") (class "Default")
      (node (ref "C94") (pin "2") (pinfunction "2_2") (pintype "passive"))
      (node (ref "C95") (pin "2") (pinfunction "2_2") (pintype "passive"))
      (node (ref "C96") (pin "1") (pinfunction "1_1") (pintype "passive"))
      (node (ref "C97") (pin "1") (pinfunction "1_1") (pintype "passive"))
      (node (ref "IC1") (pin "P15") (pinfunction "VDD18_P15") (pintype "power_in"))
      (node (ref "IC1") (pin "P7") (pinfunction "VDD18_P7") (pintype "power_in"))
      (node (ref "IC1") (pin "R10") (pinfunction "VDD18_R10") (pintype "power_in"))
      (node (ref "IC1") (pin "R14") (pinfunction "VDD18_R14") (pintype "power_in"))
    )
    (net (code "9") (name "VCC2V5") (class "Default")
      (node (ref "C100") (pin "2") (pinfunction "2_2") (pintype "passive"))
      (node (ref "C101") (pin "2") (pinfunction "2_2") (pintype "passive"))
      (node (ref "C102") (pin "2") (pinfunction "2_2") (pintype "passive"))
      (node (ref "C103") (pin "1") (pinfunction "1_1") (pintype "passive"))
      (node (ref "C104") (pin "2") (pinfunction "2_2") (pintype "passive"))
      (node (ref "C105") (pin "2") (pinfunction "2_2") (pintype "passive"))
      (node (ref "C106") (pin "1") (pinfunction "1_1") (pintype "passive"))
      (node (ref "C112") (pin "2") (pinfunction "2_2") (pintype "passive"))
      (node (ref "C113") (pin "2") (pinfunction "2_2") (pintype "passive"))
      (node (ref "C114") (pin "1") (pinfunction "1_1") (pintype "passive"))
      (node (ref "C98") (pin "2") (pinfunction "2_2") (pintype "passive"))
      (node (ref "C99") (pin "2") (pinfunction "2_2") (pintype "passive"))
      (node (ref "IC1") (pin "E6") (pinfunction "VDDAUX2_E6") (pintype "power_in"))
      (node (ref "IC1") (pin "F17") (pinfunction "VDDAUX2_F17") (pintype "power_in"))
      (node (ref "IC1") (pin "G13") (pinfunction "VDDAUX2_G13") (pintype "power_in"))
      (node (ref "IC1") (pin "G15") (pinfunction "VDD25_G15") (pintype "power_in"))
      (node (ref "IC1") (pin "G7") (pinfunction "VDD25_G7") (pintype "power_in"))
      (node (ref "IC1") (pin "G8") (pinfunction "VDDAUX2_G8") (pintype "power_in"))
      (node (ref "IC1") (pin "L19") (pinfunction "VDDA25_L19") (pintype "power_in"))
      (node (ref "IC1") (pin "L20") (pinfunction "VDDA25_L20") (pintype "power_in"))
      (node (ref "IC1") (pin "M9") (pinfunction "VDD25_M9") (pintype "power_in"))
      (node (ref "IC1") (pin "R15") (pinfunction "VDD25_R15") (pintype "power_in"))
      (node (ref "IC1") (pin "R7") (pinfunction "VDD25_R7") (pintype "power_in"))
    )
    (net (code "10") (name "VCC3V3") (class "Default")
      (node (ref "C115") (pin "2") (pinfunction "2_2") (pintype "passive"))
      (node (ref "C116") (pin "2") (pinfunction "2_2") (pintype "passive"))
      (node (ref "C117") (pin "1") (pinfunction "1_1") (pintype "passive"))
      (node (ref "IC1") (pin "J7") (pinfunction "VDDAUX4_J7") (pintype "power_in"))
      (node (ref "IC1") (pin "M7") (pinfunction "VDDAUX4_M7") (pintype "power_in"))
    )
    (net (code "11") (name "VDD25") (class "Default")
      (node (ref "C130") (pin "2") (pinfunction "2_2") (pintype "passive"))
      (node (ref "C131") (pin "2") (pinfunction "2_2") (pintype "passive"))
      (node (ref "C132") (pin "1") (pinfunction "1_1") (pintype "passive"))
      (node (ref "IC1") (pin "K17") (pinfunction "VDD_XCVR_CLK_K17") (pintype "power_in"))
      (node (ref "IC1") (pin "M17") (pinfunction "VDD_XCVR_CLK_M17") (pintype "power_in"))
    )
  )
)
